# LDO-Schematic.net
KiCad netlist of a schematic drawn in Altium Designer
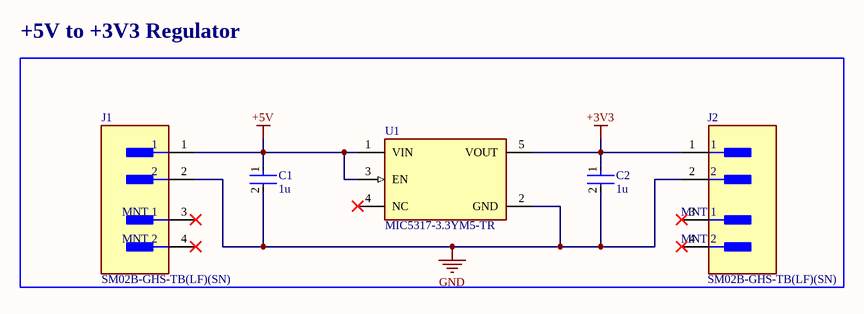
[diagram p0: LDO-Schematic.SchDoc]

(export (version "E")
  (design (tool "Eeschema 10.0.6"))
  (components
    (comp (ref "C1")
      (value "1u")
      (footprint "FP-0805-L_2_01_0_2-W_1_25-MFG")
      (description "General Purpose Ceramic Capacitor, 0805, 1uF, 10%, X7R, 15%, 10V")
      (fields (field (name "TOLERANCE") "10%") (field (name "VOLTAGE") "10V"))
      (libsource (lib "Altium Content Vault") (part "b4654b650e69147ec39a6b967a45e02"))
    )
    (comp (ref "C2")
      (value "1u")
      (footprint "FP-0805-L_2_01_0_2-W_1_25-MFG")
      (description "General Purpose Ceramic Capacitor, 0805, 1uF, 10%, X7R, 15%, 10V")
      (fields (field (name "TOLERANCE") "10%") (field (name "VOLTAGE") "10V"))
      (libsource (lib "Altium Content Vault") (part "b4654b650e69147ec39a6b967a45e02"))
    )
    (comp (ref "J1")
      (value "SM02B-GHS-TB(LF)(SN)")
      (footprint "FP-SM02B-GHS-TB_LF_SN-MFG")
      (description "CONN HEADER SMD R/A 2POS 1.25MM")
      (libsource (lib "Altium Content Vault") (part "56ec3178a87b3978bdc1b3682cd516a"))
    )
    (comp (ref "J2")
      (value "SM02B-GHS-TB(LF)(SN)")
      (footprint "FP-SM02B-GHS-TB_LF_SN-MFG")
      (description "CONN HEADER SMD R/A 2POS 1.25MM")
      (libsource (lib "") (part "56ec3178a87b3978bdc1b3682cd516a_1"))
    )
    (comp (ref "U1")
      (value "MIC5317-3.3YM5-TR")
      (footprint "FP-SOT23-5LD-PL-1-MFG")
      (description "IC REG LINEAR 3.3V 150MA SOT23-5")
      (libsource (lib "Altium Content Vault") (part "0a093dae7315cdc977fd108dde87457"))
    )
  )
  (nets
    (net (code "1") (name "+3V3") (class "Default")
      (node (ref "C2") (pin "1") (pinfunction "1_1") (pintype "passive"))
      (node (ref "J2") (pin "1") (pinfunction "1_1") (pintype "passive"))
      (node (ref "U1") (pin "5") (pinfunction "VOUT_5") (pintype "power_in"))
    )
    (net (code "2") (name "+5V") (class "Default")
      (node (ref "C1") (pin "1") (pinfunction "1_1") (pintype "passive"))
      (node (ref "J1") (pin "1") (pinfunction "1_1") (pintype "passive"))
      (node (ref "U1") (pin "1") (pinfunction "VIN_1") (pintype "power_in"))
      (node (ref "U1") (pin "3") (pinfunction "EN_3") (pintype "input"))
    )
    (net (code "3") (name "GND") (class "Default")
      (node (ref "C1") (pin "2") (pinfunction "2_2") (pintype "passive"))
      (node (ref "C2") (pin "2") (pinfunction "2_2") (pintype "passive"))
      (node (ref "J1") (pin "2") (pinfunction "2_2") (pintype "passive"))
      (node (ref "J2") (pin "2") (pinfunction "2_2") (pintype "passive"))
      (node (ref "U1") (pin "2") (pinfunction "GND_2") (pintype "power_in"))
    )
    (net (code "4") (name "unconnected-(J1-MNT_1-Pad3)") (class "Default")
      (node (ref "J1") (pin "3") (pinfunction "MNT_1_3") (pintype "passive+no_connect"))
    )
    (net (code "5") (name "unconnected-(J1-MNT_2-Pad4)") (class "Default")
      (node (ref "J1") (pin "4") (pinfunction "MNT_2_4") (pintype "passive+no_connect"))
    )
    (net (code "6") (name "unconnected-(J2-MNT_1-Pad3)") (class "Default")
      (node (ref "J2") (pin "3") (pinfunction "MNT_1_3") (pintype "passive+no_connect"))
    )
    (net (code "7") (name "unconnected-(J2-MNT_2-Pad4)") (class "Default")
      (node (ref "J2") (pin "4") (pinfunction "MNT_2_4") (pintype "passive+no_connect"))
    )
    (net (code "8") (name "unconnected-(U1-NC-Pad4)") (class "Default")
      (node (ref "U1") (pin "4") (pinfunction "NC_4") (pintype "passive+no_connect"))
    )
  )
)
